# untitled.net
KiCad netlist of a schematic drawn in EAGLE
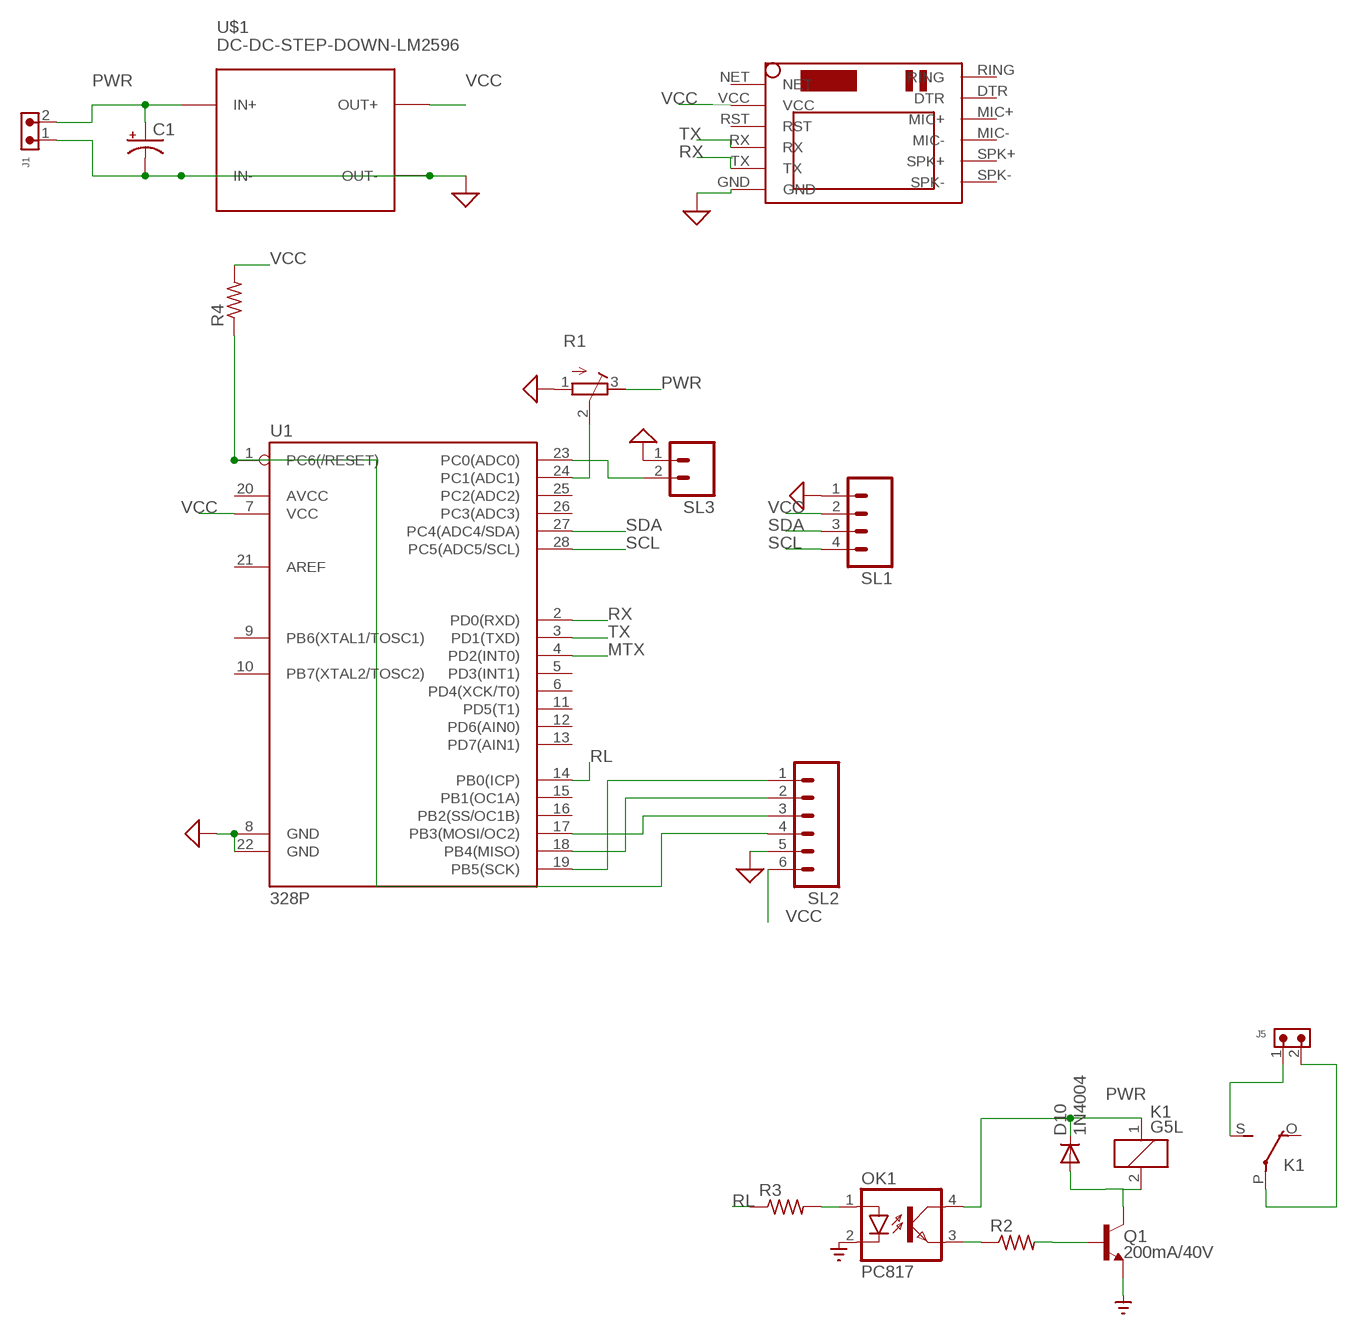
[diagram p0: schematic, sheet 1]

(export (version "E")
  (design (tool "Eeschema 10.0.6"))
  (components
    (comp (ref "C1")
      (value "CPOL-USE7.5-16")
      (footprint "eagle-import:E7,5-16")
      (libsource (lib "eagle-import") (part "CPOL-USE7.5-16"))
    )
    (comp (ref "D10")
      (value "1N4004")
      (footprint "eagle-import:DO41-10")
      (libsource (lib "eagle-import") (part "1N4004"))
    )
    (comp (ref "J1")
      (value "691305530002")
      (footprint "eagle-import:691305530002")
      (libsource (lib "eagle-import") (part "691305530002"))
    )
    (comp (ref "J5")
      (value "691305530002")
      (footprint "eagle-import:691305530002")
      (libsource (lib "eagle-import") (part "691305530002"))
    )
    (comp (ref "K1")
      (value "G5L")
      (footprint "eagle-import:G5LE")
      (libsource (lib "eagle-import") (part "G5L"))
    )
    (comp (ref "OK1")
      (value "PC817")
      (footprint "eagle-import:DIL04")
      (fields (field (name "MPN") "PC817X4J000F"))
      (libsource (lib "eagle-import") (part "PC817"))
    )
    (comp (ref "Q1")
      (value "200mA/40V")
      (footprint "eagle-import:TO-92")
      (libsource (lib "eagle-import") (part "TRANS_NPN-2N3904"))
    )
    (comp (ref "R1")
      (value "R-TRIMM3296Y")
      (footprint "eagle-import:RTRIM3296Y")
      (libsource (lib "eagle-import") (part "R-TRIMM3296Y"))
    )
    (comp (ref "R2")
      (value "R-US_0207/10")
      (footprint "eagle-import:0207_10")
      (libsource (lib "eagle-import") (part "R-US_0207/10"))
    )
    (comp (ref "R3")
      (value "R-US_0207/12")
      (footprint "eagle-import:0207_12")
      (libsource (lib "eagle-import") (part "adafruit_420_R-US_0207/12"))
    )
    (comp (ref "R4")
      (value "R-US_0207/10")
      (footprint "eagle-import:0207_10")
      (libsource (lib "eagle-import") (part "R-US_0207/10"))
    )
    (comp (ref "SL1")
      (value "M04")
      (footprint "eagle-import:04P")
      (libsource (lib "eagle-import") (part "M04"))
    )
    (comp (ref "SL2")
      (value "M06")
      (footprint "eagle-import:06P")
      (libsource (lib "eagle-import") (part "M06"))
    )
    (comp (ref "SL3")
      (value "M02")
      (footprint "eagle-import:02P")
      (libsource (lib "eagle-import") (part "M02"))
    )
    (comp (ref "U$1")
      (value "DC-DC-STEP-DOWN-LM2596")
      (footprint "eagle-import:DC-DC-STEP-DOWN-LM2596")
      (libsource (lib "eagle-import") (part "DC-DC-STEP-DOWN-LM2596"))
    )
    (comp (ref "U$2")
      (value "SIM800LMODULE")
      (footprint "eagle-import:SIM800LMODULE")
      (libsource (lib "eagle-import") (part "SIM800LMODULE"))
    )
    (comp (ref "U1")
      (value "328P")
      (footprint "eagle-import:DIP28")
      (libsource (lib "eagle-import") (part "ATMEGA328P_PDIP"))
    )
  )
  (nets
    (net (code "1") (name "/MTX") (class "Default")
      (node (ref "U1") (pin "4") (pinfunction "PD2(INT0)_4") (pintype "bidirectional"))
    )
    (net (code "2") (name "/PWR") (class "Default")
      (node (ref "C1") (pin "+") (pinfunction "+_+") (pintype "passive"))
      (node (ref "D10") (pin "C") (pinfunction "C_C") (pintype "passive"))
      (node (ref "J1") (pin "2") (pinfunction "2_2") (pintype "passive"))
      (node (ref "K1") (pin "1") (pinfunction "1_1") (pintype "passive"))
      (node (ref "OK1") (pin "4") (pinfunction "COL_4") (pintype "passive"))
      (node (ref "R1") (pin "3") (pinfunction "E_3") (pintype "passive"))
      (node (ref "U$1") (pin "IN+") (pinfunction "IN+_IN+") (pintype "bidirectional"))
    )
    (net (code "3") (name "/RL") (class "Default")
      (node (ref "R3") (pin "1") (pinfunction "1_1") (pintype "passive"))
      (node (ref "U1") (pin "14") (pinfunction "PB0(ICP)_14") (pintype "bidirectional"))
    )
    (net (code "4") (name "/RX") (class "Default")
      (node (ref "U$2") (pin "TX") (pinfunction "TX_TX") (pintype "bidirectional"))
      (node (ref "U1") (pin "2") (pinfunction "PD0(RXD)_2") (pintype "bidirectional"))
    )
    (net (code "5") (name "/SCL") (class "Default")
      (node (ref "SL1") (pin "4") (pinfunction "4_4") (pintype "passive"))
      (node (ref "U1") (pin "28") (pinfunction "PC5(ADC5/SCL)_28") (pintype "bidirectional"))
    )
    (net (code "6") (name "/SDA") (class "Default")
      (node (ref "SL1") (pin "3") (pinfunction "3_3") (pintype "passive"))
      (node (ref "U1") (pin "27") (pinfunction "PC4(ADC4/SDA)_27") (pintype "bidirectional"))
    )
    (net (code "7") (name "/TX") (class "Default")
      (node (ref "U$2") (pin "RX") (pinfunction "RX_RX") (pintype "bidirectional"))
      (node (ref "U1") (pin "3") (pinfunction "PD1(TXD)_3") (pintype "bidirectional"))
    )
    (net (code "8") (name "/VCC") (class "Default")
      (node (ref "R4") (pin "2") (pinfunction "2_2") (pintype "passive"))
      (node (ref "SL1") (pin "2") (pinfunction "2_2") (pintype "passive"))
      (node (ref "SL2") (pin "6") (pinfunction "6_6") (pintype "passive"))
      (node (ref "U$1") (pin "OUT+") (pinfunction "OUT+_OUT+") (pintype "bidirectional"))
      (node (ref "U$2") (pin "VCC") (pinfunction "VCC_VCC") (pintype "bidirectional"))
      (node (ref "U1") (pin "7") (pinfunction "VCC_7") (pintype "bidirectional"))
    )
    (net (code "9") (name "Net-(J5-Pad1)") (class "Default")
      (node (ref "J5") (pin "1") (pinfunction "1_1") (pintype "passive"))
      (node (ref "K1") (pin "S") (pinfunction "S_S") (pintype "passive"))
    )
    (net (code "10") (name "Net-(J5-Pad2)") (class "Default")
      (node (ref "J5") (pin "2") (pinfunction "2_2") (pintype "passive"))
      (node (ref "K1") (pin "P") (pinfunction "P_P") (pintype "passive"))
    )
    (net (code "11") (name "Net-(OK1-A)") (class "Default")
      (node (ref "OK1") (pin "1") (pinfunction "A_1") (pintype "passive"))
      (node (ref "R3") (pin "2") (pinfunction "2_2") (pintype "passive"))
    )
    (net (code "12") (name "Net-(OK1-EMIT)") (class "Default")
      (node (ref "OK1") (pin "3") (pinfunction "EMIT_3") (pintype "passive"))
      (node (ref "R2") (pin "1") (pinfunction "1_1") (pintype "passive"))
    )
    (net (code "13") (name "Net-(Q1-B)") (class "Default")
      (node (ref "Q1") (pin "2") (pinfunction "B_2") (pintype "passive"))
      (node (ref "R2") (pin "2") (pinfunction "2_2") (pintype "passive"))
    )
    (net (code "14") (name "Net-(Q1-C)") (class "Default")
      (node (ref "D10") (pin "A") (pinfunction "A_A") (pintype "passive"))
      (node (ref "K1") (pin "2") (pinfunction "2_2") (pintype "passive"))
      (node (ref "Q1") (pin "3") (pinfunction "C_3") (pintype "passive"))
    )
    (net (code "15") (name "Net-(R1-S)") (class "Default")
      (node (ref "R1") (pin "2") (pinfunction "S_2") (pintype "passive"))
      (node (ref "U1") (pin "24") (pinfunction "PC1(ADC1)_24") (pintype "bidirectional"))
    )
    (net (code "16") (name "Net-(U1-PB3(MOSI{slash}OC2))") (class "Default")
      (node (ref "SL2") (pin "3") (pinfunction "3_3") (pintype "passive"))
      (node (ref "U1") (pin "17") (pinfunction "PB3(MOSI/OC2)_17") (pintype "bidirectional"))
    )
    (net (code "17") (name "Net-(U1-PB4(MISO))") (class "Default")
      (node (ref "SL2") (pin "2") (pinfunction "2_2") (pintype "passive"))
      (node (ref "U1") (pin "18") (pinfunction "PB4(MISO)_18") (pintype "bidirectional"))
    )
    (net (code "18") (name "Net-(U1-PB5(SCK))") (class "Default")
      (node (ref "SL2") (pin "1") (pinfunction "1_1") (pintype "passive"))
      (node (ref "U1") (pin "19") (pinfunction "PB5(SCK)_19") (pintype "bidirectional"))
    )
    (net (code "19") (name "Net-(U1-PC0(ADC0))") (class "Default")
      (node (ref "SL3") (pin "2") (pinfunction "2_2") (pintype "passive"))
      (node (ref "U1") (pin "23") (pinfunction "PC0(ADC0)_23") (pintype "bidirectional"))
    )
    (net (code "20") (name "Net-(U1-PC6({slash}RESET))") (class "Default")
      (node (ref "R4") (pin "1") (pinfunction "1_1") (pintype "passive"))
      (node (ref "SL2") (pin "4") (pinfunction "4_4") (pintype "passive"))
      (node (ref "U1") (pin "1") (pinfunction "PC6(/RESET)_1") (pintype "bidirectional"))
    )
    (net (code "21") (name "SUP") (class "Default")
      (node (ref "C1") (pin "-") (pinfunction "-_-") (pintype "passive"))
      (node (ref "J1") (pin "1") (pinfunction "1_1") (pintype "passive"))
      (node (ref "OK1") (pin "2") (pinfunction "C_2") (pintype "passive"))
      (node (ref "Q1") (pin "1") (pinfunction "E_1") (pintype "passive"))
      (node (ref "R1") (pin "1") (pinfunction "A_1") (pintype "passive"))
      (node (ref "SL1") (pin "1") (pinfunction "1_1") (pintype "passive"))
      (node (ref "SL2") (pin "5") (pinfunction "5_5") (pintype "passive"))
      (node (ref "SL3") (pin "1") (pinfunction "1_1") (pintype "passive"))
      (node (ref "U$1") (pin "IN-") (pinfunction "IN-_IN-") (pintype "bidirectional"))
      (node (ref "U$1") (pin "OUT-") (pinfunction "OUT-_OUT-") (pintype "bidirectional"))
      (node (ref "U$2") (pin "GND") (pinfunction "GND_GND") (pintype "bidirectional"))
      (node (ref "U1") (pin "22") (pinfunction "GND_22") (pintype "bidirectional"))
      (node (ref "U1") (pin "8") (pinfunction "GND_8") (pintype "bidirectional"))
    )
    (net (code "22") (name "unconnected-(K1-PadO)") (class "Default")
      (node (ref "K1") (pin "O") (pinfunction "O_O") (pintype "passive"))
    )
    (net (code "23") (name "unconnected-(U$2-PadDTR)") (class "Default")
      (node (ref "U$2") (pin "DTR") (pinfunction "DTR_DTR") (pintype "bidirectional"))
    )
    (net (code "24") (name "unconnected-(U$2-PadMIC+)") (class "Default")
      (node (ref "U$2") (pin "MIC+") (pinfunction "MIC+_MIC+") (pintype "bidirectional"))
    )
    (net (code "25") (name "unconnected-(U$2-PadMIC-)") (class "Default")
      (node (ref "U$2") (pin "MIC-") (pinfunction "MIC-_MIC-") (pintype "bidirectional"))
    )
    (net (code "26") (name "unconnected-(U$2-PadNET)") (class "Default")
      (node (ref "U$2") (pin "NET") (pinfunction "NET_NET") (pintype "bidirectional"))
    )
    (net (code "27") (name "unconnected-(U$2-PadRING)") (class "Default")
      (node (ref "U$2") (pin "RING") (pinfunction "RING_RING") (pintype "bidirectional"))
    )
    (net (code "28") (name "unconnected-(U$2-PadRST)") (class "Default")
      (node (ref "U$2") (pin "RST") (pinfunction "RST_RST") (pintype "bidirectional"))
    )
    (net (code "29") (name "unconnected-(U$2-PadSPK+)") (class "Default")
      (node (ref "U$2") (pin "SPK+") (pinfunction "SPK+_SPK+") (pintype "bidirectional"))
    )
    (net (code "30") (name "unconnected-(U$2-PadSPK-)") (class "Default")
      (node (ref "U$2") (pin "SPK-") (pinfunction "SPK-_SPK-") (pintype "bidirectional"))
    )
    (net (code "31") (name "unconnected-(U1-AREF-Pad21)") (class "Default")
      (node (ref "U1") (pin "21") (pinfunction "AREF_21") (pintype "bidirectional"))
    )
    (net (code "32") (name "unconnected-(U1-AVCC-Pad20)") (class "Default")
      (node (ref "U1") (pin "20") (pinfunction "AVCC_20") (pintype "bidirectional"))
    )
    (net (code "33") (name "unconnected-(U1-PB1(OC1A)-Pad15)") (class "Default")
      (node (ref "U1") (pin "15") (pinfunction "PB1(OC1A)_15") (pintype "bidirectional"))
    )
    (net (code "34") (name "unconnected-(U1-PB2(SS{slash}OC1B)-Pad16)") (class "Default")
      (node (ref "U1") (pin "16") (pinfunction "PB2(SS/OC1B)_16") (pintype "bidirectional"))
    )
    (net (code "35") (name "unconnected-(U1-PB6(XTAL1{slash}TOSC1)-Pad9)") (class "Default")
      (node (ref "U1") (pin "9") (pinfunction "PB6(XTAL1/TOSC1)_9") (pintype "bidirectional"))
    )
    (net (code "36") (name "unconnected-(U1-PB7(XTAL2{slash}TOSC2)-Pad10)") (class "Default")
      (node (ref "U1") (pin "10") (pinfunction "PB7(XTAL2/TOSC2)_10") (pintype "bidirectional"))
    )
    (net (code "37") (name "unconnected-(U1-PC2(ADC2)-Pad25)") (class "Default")
      (node (ref "U1") (pin "25") (pinfunction "PC2(ADC2)_25") (pintype "bidirectional"))
    )
    (net (code "38") (name "unconnected-(U1-PC3(ADC3)-Pad26)") (class "Default")
      (node (ref "U1") (pin "26") (pinfunction "PC3(ADC3)_26") (pintype "bidirectional"))
    )
    (net (code "39") (name "unconnected-(U1-PD3(INT1)-Pad5)") (class "Default")
      (node (ref "U1") (pin "5") (pinfunction "PD3(INT1)_5") (pintype "bidirectional"))
    )
    (net (code "40") (name "unconnected-(U1-PD4(XCK{slash}T0)-Pad6)") (class "Default")
      (node (ref "U1") (pin "6") (pinfunction "PD4(XCK/T0)_6") (pintype "bidirectional"))
    )
    (net (code "41") (name "unconnected-(U1-PD5(T1)-Pad11)") (class "Default")
      (node (ref "U1") (pin "11") (pinfunction "PD5(T1)_11") (pintype "bidirectional"))
    )
    (net (code "42") (name "unconnected-(U1-PD6(AIN0)-Pad12)") (class "Default")
      (node (ref "U1") (pin "12") (pinfunction "PD6(AIN0)_12") (pintype "bidirectional"))
    )
    (net (code "43") (name "unconnected-(U1-PD7(AIN1)-Pad13)") (class "Default")
      (node (ref "U1") (pin "13") (pinfunction "PD7(AIN1)_13") (pintype "bidirectional"))
    )
  )
)
